# IOpin.net
KiCad netlist of a schematic drawn in Altium Designer
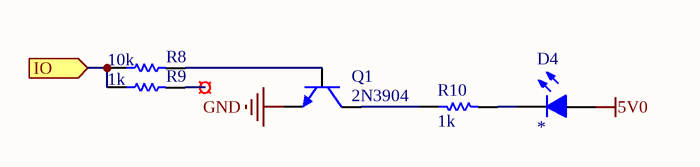
[diagram p0: IOpin.SchDoc]

(export (version "E")
  (design (tool "Eeschema 10.0.6"))
  (components
    (comp (ref "D4")
      (value "~")
      (footprint "LED-0603-K1A2")
      (description "2 Pin LED K1A2")
      (fields (field (name "LABEL") "*"))
      (libsource (lib "Semiconductors") (part "-LED K1A2"))
    )
    (comp (ref "Q1")
      (value "2N3904")
      (footprint "SOT95P245X110-3N")
      (description "NPN General Purpose Amplifier")
      (fields (field (name "PUBLISHER") "Altium Limited"))
      (libsource (lib "Austin_Components") (part "2N3904"))
    )
    (comp (ref "R8")
      (value "10k")
      (footprint "RES 0603_N")
      (description "Resistor")
      (fields (field (name "Comment") "Res") (field (name "PUBLISHER") "Altium Limited"))
      (libsource (lib "Austin_Components") (part "Res"))
    )
    (comp (ref "R9")
      (value "1k")
      (footprint "RES 0603_N")
      (description "Resistor")
      (fields (field (name "Comment") "Res") (field (name "PUBLISHER") "Altium Limited"))
      (libsource (lib "Austin_Components") (part "Res"))
    )
    (comp (ref "R10")
      (value "1k")
      (footprint "RES 0603_N")
      (description "Resistor")
      (fields (field (name "Comment") "Res") (field (name "PUBLISHER") "Altium Limited"))
      (libsource (lib "Austin_Components") (part "Res"))
    )
    (comp (ref "TP31") (value "~") (footprint "THTP") (libsource (lib "A_Speciality") (part "THTP")))
  )
  (nets
    (net (code "1") (name "/IO") (class "Default")
      (node (ref "R8") (pin "1") (pinfunction "1_1") (pintype "passive"))
      (node (ref "R9") (pin "1") (pinfunction "1_1") (pintype "passive"))
    )
    (net (code "2") (name "5V0") (class "Default")
      (node (ref "D4") (pin "2") (pinfunction "A_2") (pintype "passive"))
    )
    (net (code "3") (name "GND") (class "Default")
      (node (ref "Q1") (pin "2") (pinfunction "E_2") (pintype "passive"))
    )
    (net (code "4") (name "Net-(D4-K)") (class "Default")
      (node (ref "D4") (pin "1") (pinfunction "K_1") (pintype "passive"))
      (node (ref "R10") (pin "2") (pinfunction "2_2") (pintype "passive"))
    )
    (net (code "5") (name "Net-(Q1-B)") (class "Default")
      (node (ref "Q1") (pin "1") (pinfunction "B_1") (pintype "passive"))
      (node (ref "R8") (pin "2") (pinfunction "2_2") (pintype "passive"))
    )
    (net (code "6") (name "Net-(Q1-C)") (class "Default")
      (node (ref "Q1") (pin "3") (pinfunction "C_3") (pintype "passive"))
      (node (ref "R10") (pin "1") (pinfunction "1_1") (pintype "passive"))
    )
    (net (code "7") (name "Net-(R9-Pad2)") (class "Default")
      (node (ref "R9") (pin "2") (pinfunction "2_2") (pintype "passive"))
      (node (ref "TP31") (pin "1") (pintype "passive"))
    )
  )
)
